# mainboard.net
KiCad netlist of a schematic drawn in EAGLE
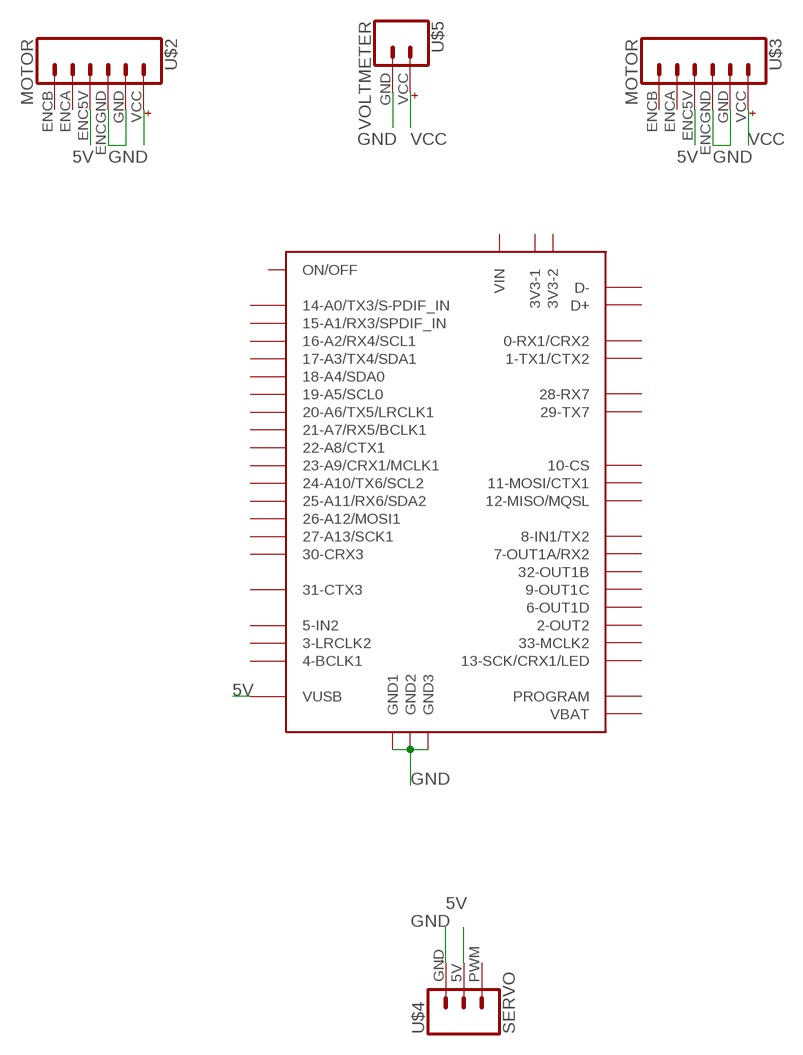
[diagram p0: schematic, sheet 1]

(export (version "E")
  (design (tool "Eeschema 10.0.6"))
  (components
    (comp (ref "U$1")
      (value "TEENSY40")
      (footprint "eagle-import:TEENSY40")
      (libsource (lib "eagle-import") (part "TEENSY40"))
    )
    (comp (ref "U$2")
      (value "MOTOR")
      (footprint "eagle-import:MOTOR")
      (libsource (lib "eagle-import") (part "MOTOR"))
    )
    (comp (ref "U$3")
      (value "MOTOR")
      (footprint "eagle-import:MOTOR")
      (libsource (lib "eagle-import") (part "MOTOR"))
    )
    (comp (ref "U$4")
      (value "SERVO")
      (footprint "eagle-import:SERVO")
      (libsource (lib "eagle-import") (part "SERVO"))
    )
    (comp (ref "U$5")
      (value "VOLTMETER")
      (footprint "eagle-import:VOLTMETER")
      (libsource (lib "eagle-import") (part "VOLTMETER"))
    )
  )
  (nets
    (net (code "1") (name "/5V") (class "Default")
      (node (ref "U$1") (pin "VUSB") (pinfunction "VUSB_VUSB") (pintype "bidirectional"))
      (node (ref "U$2") (pin "ENC5V") (pinfunction "ENC5V_ENC5V") (pintype "passive"))
      (node (ref "U$3") (pin "ENC5V") (pinfunction "ENC5V_ENC5V") (pintype "passive"))
      (node (ref "U$4") (pin "5V") (pinfunction "5V_5V") (pintype "passive"))
    )
    (net (code "2") (name "/GND") (class "Default")
      (node (ref "U$1") (pin "GND1") (pinfunction "GND1_GND1") (pintype "bidirectional"))
      (node (ref "U$1") (pin "GND2") (pinfunction "GND2_GND2") (pintype "bidirectional"))
      (node (ref "U$1") (pin "GND3") (pinfunction "GND3_GND3") (pintype "bidirectional"))
      (node (ref "U$2") (pin "ENCGND") (pinfunction "ENCGND_ENCGND") (pintype "passive"))
      (node (ref "U$2") (pin "GND") (pinfunction "GND_GND") (pintype "passive"))
      (node (ref "U$3") (pin "ENCGND") (pinfunction "ENCGND_ENCGND") (pintype "passive"))
      (node (ref "U$3") (pin "GND") (pinfunction "GND_GND") (pintype "passive"))
      (node (ref "U$4") (pin "GND") (pinfunction "GND_GND") (pintype "passive"))
      (node (ref "U$5") (pin "GND") (pinfunction "GND_GND") (pintype "passive"))
    )
    (net (code "3") (name "/VCC") (class "Default")
      (node (ref "U$3") (pin "VCC") (pinfunction "VCC_VCC") (pintype "passive"))
      (node (ref "U$5") (pin "VCC") (pinfunction "VCC_VCC") (pintype "passive"))
    )
    (net (code "4") (name "unconnected-(U$1-0-RX1{slash}CRX2-Pad0-RX1)") (class "Default")
      (node (ref "U$1") (pin "0-RX1") (pinfunction "0-RX1/CRX2_0-RX1") (pintype "bidirectional"))
    )
    (net (code "5") (name "unconnected-(U$1-1-TX1{slash}CTX2-Pad1-TX1)") (class "Default")
      (node (ref "U$1") (pin "1-TX1") (pinfunction "1-TX1/CTX2_1-TX1") (pintype "bidirectional"))
    )
    (net (code "6") (name "unconnected-(U$1-4-BCLK1-Pad4-BCLK2)") (class "Default")
      (node (ref "U$1") (pin "4-BCLK2") (pinfunction "4-BCLK1_4-BCLK2") (pintype "bidirectional"))
    )
    (net (code "7") (name "unconnected-(U$1-7-OUT1A{slash}RX2-Pad7-RX2{slash}OUT1A)") (class "Default")
      (node (ref "U$1") (pin "7-RX2/OUT1A") (pinfunction "7-OUT1A/RX2_7-RX2/OUT1A") (pintype "bidirectional"))
    )
    (net (code "8") (name "unconnected-(U$1-8-IN1{slash}TX2-Pad8-TX2{slash}IN1)") (class "Default")
      (node (ref "U$1") (pin "8-TX2/IN1") (pinfunction "8-IN1/TX2_8-TX2/IN1") (pintype "bidirectional"))
    )
    (net (code "9") (name "unconnected-(U$1-10-CS-Pad10-CS{slash}MQSR)") (class "Default")
      (node (ref "U$1") (pin "10-CS/MQSR") (pinfunction "10-CS_10-CS/MQSR") (pintype "bidirectional"))
    )
    (net (code "10") (name "unconnected-(U$1-12-MISO{slash}MQSL-Pad12-MIO{slash}MQSL)") (class "Default")
      (node (ref "U$1") (pin "12-MIO/MQSL") (pinfunction "12-MISO/MQSL_12-MIO/MQSL") (pintype "bidirectional"))
    )
    (net (code "11") (name "unconnected-(U$1-14-A0{slash}TX3{slash}S-PDIF_IN-Pad14-A0{slash}TX3{slash}S-PFI_OUT)") (class "Default")
      (node (ref "U$1") (pin "14-A0/TX3/S-PFI_OUT") (pinfunction "14-A0/TX3/S-PDIF_IN_14-A0/TX3/S-PFI_OUT") (pintype "bidirectional"))
    )
    (net (code "12") (name "unconnected-(U$1-15-A1{slash}RX3{slash}SPDIF_IN-Pad15-A1{slash}RX3{slash}S-PDIF_IN)") (class "Default")
      (node (ref "U$1") (pin "15-A1/RX3/S-PDIF_IN") (pinfunction "15-A1/RX3/SPDIF_IN_15-A1/RX3/S-PDIF_IN") (pintype "bidirectional"))
    )
    (net (code "13") (name "unconnected-(U$1-23-A9{slash}CRX1{slash}MCLK1-Pad23-A9{slash}CRX1{slash}CCLK1)") (class "Default")
      (node (ref "U$1") (pin "23-A9/CRX1/CCLK1") (pinfunction "23-A9/CRX1/MCLK1_23-A9/CRX1/CCLK1") (pintype "bidirectional"))
    )
    (net (code "14") (name "unconnected-(U$1-25-A11{slash}RX6{slash}SDA2-Pad25-A11{slash}SDA2)") (class "Default")
      (node (ref "U$1") (pin "25-A11/SDA2") (pinfunction "25-A11/RX6/SDA2_25-A11/SDA2") (pintype "bidirectional"))
    )
    (net (code "15") (name "unconnected-(U$1-32-OUT1B-Pad32-OUTB1)") (class "Default")
      (node (ref "U$1") (pin "32-OUTB1") (pinfunction "32-OUT1B_32-OUTB1") (pintype "bidirectional"))
    )
    (net (code "16") (name "unconnected-(U$1-Pad2-OUT2)") (class "Default")
      (node (ref "U$1") (pin "2-OUT2") (pinfunction "2-OUT2_2-OUT2") (pintype "bidirectional"))
    )
    (net (code "17") (name "unconnected-(U$1-Pad3-LRCLK2)") (class "Default")
      (node (ref "U$1") (pin "3-LRCLK2") (pinfunction "3-LRCLK2_3-LRCLK2") (pintype "bidirectional"))
    )
    (net (code "18") (name "unconnected-(U$1-Pad3V3-1)") (class "Default")
      (node (ref "U$1") (pin "3V3-1") (pinfunction "3V3-1_3V3-1") (pintype "bidirectional"))
    )
    (net (code "19") (name "unconnected-(U$1-Pad3V3-2)") (class "Default")
      (node (ref "U$1") (pin "3V3-2") (pinfunction "3V3-2_3V3-2") (pintype "bidirectional"))
    )
    (net (code "20") (name "unconnected-(U$1-Pad5-IN2)") (class "Default")
      (node (ref "U$1") (pin "5-IN2") (pinfunction "5-IN2_5-IN2") (pintype "bidirectional"))
    )
    (net (code "21") (name "unconnected-(U$1-Pad6-OUT1D)") (class "Default")
      (node (ref "U$1") (pin "6-OUT1D") (pinfunction "6-OUT1D_6-OUT1D") (pintype "bidirectional"))
    )
    (net (code "22") (name "unconnected-(U$1-Pad9-OUT1C)") (class "Default")
      (node (ref "U$1") (pin "9-OUT1C") (pinfunction "9-OUT1C_9-OUT1C") (pintype "bidirectional"))
    )
    (net (code "23") (name "unconnected-(U$1-Pad11-MOSI{slash}CTX1)") (class "Default")
      (node (ref "U$1") (pin "11-MOSI/CTX1") (pinfunction "11-MOSI/CTX1_11-MOSI/CTX1") (pintype "bidirectional"))
    )
    (net (code "24") (name "unconnected-(U$1-Pad13-SCK{slash}CRX1{slash}LED)") (class "Default")
      (node (ref "U$1") (pin "13-SCK/CRX1/LED") (pinfunction "13-SCK/CRX1/LED_13-SCK/CRX1/LED") (pintype "bidirectional"))
    )
    (net (code "25") (name "unconnected-(U$1-Pad16-A2{slash}RX4{slash}SCL1)") (class "Default")
      (node (ref "U$1") (pin "16-A2/RX4/SCL1") (pinfunction "16-A2/RX4/SCL1_16-A2/RX4/SCL1") (pintype "bidirectional"))
    )
    (net (code "26") (name "unconnected-(U$1-Pad17-A3{slash}TX4{slash}SDA1)") (class "Default")
      (node (ref "U$1") (pin "17-A3/TX4/SDA1") (pinfunction "17-A3/TX4/SDA1_17-A3/TX4/SDA1") (pintype "bidirectional"))
    )
    (net (code "27") (name "unconnected-(U$1-Pad18-A4{slash}SDA0)") (class "Default")
      (node (ref "U$1") (pin "18-A4/SDA0") (pinfunction "18-A4/SDA0_18-A4/SDA0") (pintype "bidirectional"))
    )
    (net (code "28") (name "unconnected-(U$1-Pad19-A5{slash}SCL0)") (class "Default")
      (node (ref "U$1") (pin "19-A5/SCL0") (pinfunction "19-A5/SCL0_19-A5/SCL0") (pintype "bidirectional"))
    )
    (net (code "29") (name "unconnected-(U$1-Pad20-A6{slash}TX5{slash}LRCLK1)") (class "Default")
      (node (ref "U$1") (pin "20-A6/TX5/LRCLK1") (pinfunction "20-A6/TX5/LRCLK1_20-A6/TX5/LRCLK1") (pintype "bidirectional"))
    )
    (net (code "30") (name "unconnected-(U$1-Pad21-A7{slash}RX5{slash}BCLK1)") (class "Default")
      (node (ref "U$1") (pin "21-A7/RX5/BCLK1") (pinfunction "21-A7/RX5/BCLK1_21-A7/RX5/BCLK1") (pintype "bidirectional"))
    )
    (net (code "31") (name "unconnected-(U$1-Pad22-A8{slash}CTX1)") (class "Default")
      (node (ref "U$1") (pin "22-A8/CTX1") (pinfunction "22-A8/CTX1_22-A8/CTX1") (pintype "bidirectional"))
    )
    (net (code "32") (name "unconnected-(U$1-Pad24-A10{slash}TX6{slash}SCL2)") (class "Default")
      (node (ref "U$1") (pin "24-A10/TX6/SCL2") (pinfunction "24-A10/TX6/SCL2_24-A10/TX6/SCL2") (pintype "bidirectional"))
    )
    (net (code "33") (name "unconnected-(U$1-Pad26-A12{slash}MOSI1)") (class "Default")
      (node (ref "U$1") (pin "26-A12/MOSI1") (pinfunction "26-A12/MOSI1_26-A12/MOSI1") (pintype "bidirectional"))
    )
    (net (code "34") (name "unconnected-(U$1-Pad27-A13{slash}SCK1)") (class "Default")
      (node (ref "U$1") (pin "27-A13/SCK1") (pinfunction "27-A13/SCK1_27-A13/SCK1") (pintype "bidirectional"))
    )
    (net (code "35") (name "unconnected-(U$1-Pad28-RX7)") (class "Default")
      (node (ref "U$1") (pin "28-RX7") (pinfunction "28-RX7_28-RX7") (pintype "bidirectional"))
    )
    (net (code "36") (name "unconnected-(U$1-Pad29-TX7)") (class "Default")
      (node (ref "U$1") (pin "29-TX7") (pinfunction "29-TX7_29-TX7") (pintype "bidirectional"))
    )
    (net (code "37") (name "unconnected-(U$1-Pad30-CRX3)") (class "Default")
      (node (ref "U$1") (pin "30-CRX3") (pinfunction "30-CRX3_30-CRX3") (pintype "bidirectional"))
    )
    (net (code "38") (name "unconnected-(U$1-Pad31-CTX3)") (class "Default")
      (node (ref "U$1") (pin "31-CTX3") (pinfunction "31-CTX3_31-CTX3") (pintype "bidirectional"))
    )
    (net (code "39") (name "unconnected-(U$1-Pad33-MCLK2)") (class "Default")
      (node (ref "U$1") (pin "33-MCLK2") (pinfunction "33-MCLK2_33-MCLK2") (pintype "bidirectional"))
    )
    (net (code "40") (name "unconnected-(U$1-PadD+)") (class "Default")
      (node (ref "U$1") (pin "D+") (pinfunction "D+_D+") (pintype "bidirectional"))
    )
    (net (code "41") (name "unconnected-(U$1-PadD-)") (class "Default")
      (node (ref "U$1") (pin "D-") (pinfunction "D-_D-") (pintype "bidirectional"))
    )
    (net (code "42") (name "unconnected-(U$1-PadON{slash}OFF)") (class "Default")
      (node (ref "U$1") (pin "ON/OFF") (pinfunction "ON/OFF_ON/OFF") (pintype "bidirectional"))
    )
    (net (code "43") (name "unconnected-(U$1-PadPROGRAM)") (class "Default")
      (node (ref "U$1") (pin "PROGRAM") (pinfunction "PROGRAM_PROGRAM") (pintype "bidirectional"))
    )
    (net (code "44") (name "unconnected-(U$1-PadVBAT)") (class "Default")
      (node (ref "U$1") (pin "VBAT") (pinfunction "VBAT_VBAT") (pintype "bidirectional"))
    )
    (net (code "45") (name "unconnected-(U$1-PadVIN)") (class "Default")
      (node (ref "U$1") (pin "VIN") (pinfunction "VIN_VIN") (pintype "bidirectional"))
    )
    (net (code "46") (name "unconnected-(U$2-PadENCA)") (class "Default")
      (node (ref "U$2") (pin "ENCA") (pinfunction "ENCA_ENCA") (pintype "passive"))
    )
    (net (code "47") (name "unconnected-(U$2-PadENCB)") (class "Default")
      (node (ref "U$2") (pin "ENCB") (pinfunction "ENCB_ENCB") (pintype "passive"))
    )
    (net (code "48") (name "unconnected-(U$2-PadVCC)") (class "Default")
      (node (ref "U$2") (pin "VCC") (pinfunction "VCC_VCC") (pintype "passive"))
    )
    (net (code "49") (name "unconnected-(U$3-PadENCA)") (class "Default")
      (node (ref "U$3") (pin "ENCA") (pinfunction "ENCA_ENCA") (pintype "passive"))
    )
    (net (code "50") (name "unconnected-(U$3-PadENCB)") (class "Default")
      (node (ref "U$3") (pin "ENCB") (pinfunction "ENCB_ENCB") (pintype "passive"))
    )
    (net (code "51") (name "unconnected-(U$4-PadPWM)") (class "Default")
      (node (ref "U$4") (pin "PWM") (pinfunction "PWM_PWM") (pintype "passive"))
    )
  )
)
